# 19-CPLD.net
KiCad netlist of a schematic drawn in Altium Designer
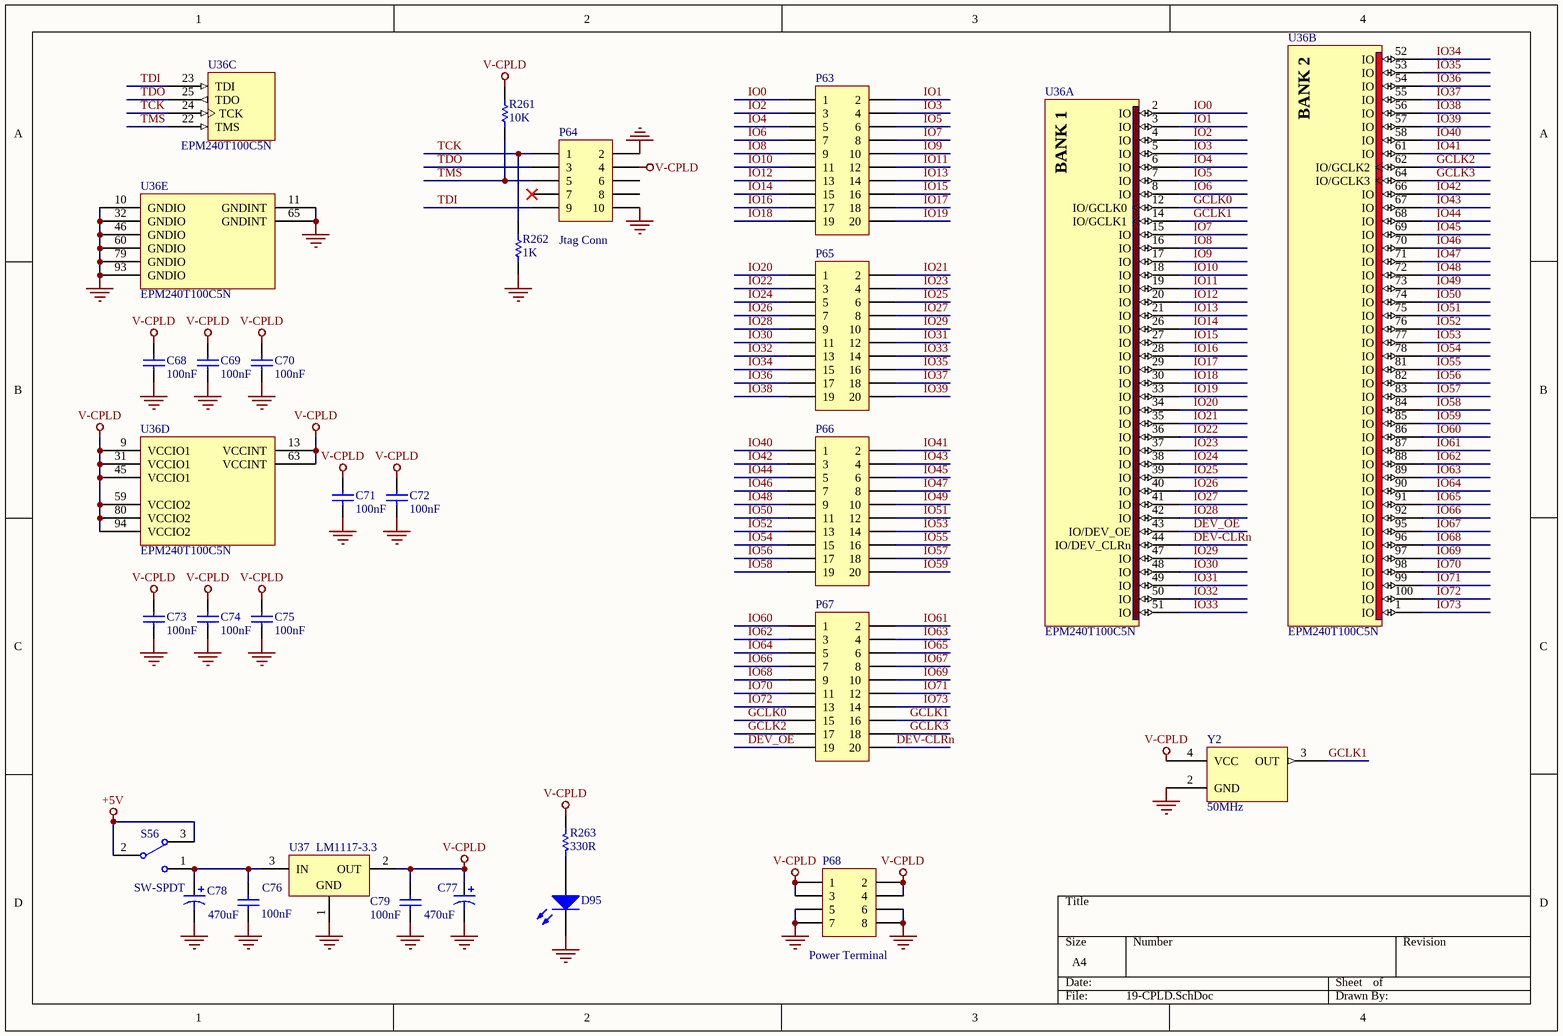
[diagram p0: 19-CPLD.SchDoc]

(export (version "E")
  (design (tool "Eeschema 10.0.6"))
  (components
    (comp (ref "C68")
      (value "100nF")
      (footprint "c-0805")
      (description "Capacitor")
      (fields (field (name "Comment") "104") (field (name "PUBLISHER") "Altium Limited"))
      (libsource (lib "Miscellaneous Devices") (part "Cap"))
    )
    (comp (ref "C69")
      (value "100nF")
      (footprint "c-0805")
      (description "Capacitor")
      (fields (field (name "Comment") "104") (field (name "PUBLISHER") "Altium Limited"))
      (libsource (lib "Miscellaneous Devices") (part "Cap"))
    )
    (comp (ref "C70")
      (value "100nF")
      (footprint "c-0805")
      (description "Capacitor")
      (fields (field (name "Comment") "104") (field (name "PUBLISHER") "Altium Limited"))
      (libsource (lib "Miscellaneous Devices") (part "Cap"))
    )
    (comp (ref "C71")
      (value "100nF")
      (footprint "c-0805")
      (description "Capacitor")
      (fields (field (name "Comment") "104") (field (name "PUBLISHER") "Altium Limited"))
      (libsource (lib "Miscellaneous Devices") (part "Cap"))
    )
    (comp (ref "C72")
      (value "100nF")
      (footprint "c-0805")
      (description "Capacitor")
      (fields (field (name "Comment") "104") (field (name "PUBLISHER") "Altium Limited"))
      (libsource (lib "Miscellaneous Devices") (part "Cap"))
    )
    (comp (ref "C73")
      (value "100nF")
      (footprint "c-0805")
      (description "Capacitor")
      (fields (field (name "Comment") "104") (field (name "PUBLISHER") "Altium Limited"))
      (libsource (lib "Miscellaneous Devices") (part "Cap"))
    )
    (comp (ref "C74")
      (value "100nF")
      (footprint "c-0805")
      (description "Capacitor")
      (fields (field (name "Comment") "104") (field (name "PUBLISHER") "Altium Limited"))
      (libsource (lib "Miscellaneous Devices") (part "Cap"))
    )
    (comp (ref "C75")
      (value "100nF")
      (footprint "c-0805")
      (description "Capacitor")
      (fields (field (name "Comment") "104") (field (name "PUBLISHER") "Altium Limited"))
      (libsource (lib "Miscellaneous Devices") (part "Cap"))
    )
    (comp (ref "C76")
      (value "100nF")
      (footprint "c-0805")
      (description "Capacitor")
      (fields
        (field (name "MANUFACTURER") "Generic Components")
        (field (name "Comment") "104")
        (field (name "PUBLISHER") "Altium Hobart Technology Centre")
      )
      (libsource (lib "Miscellaneous Devices") (part "Cap"))
    )
    (comp (ref "C77")
      (value "470uF")
      (footprint "C-ALU-10x10mm")
      (description "Polarized Capacitor (Radial)")
      (fields (field (name "Comment") "470uF/16V") (field (name "PUBLISHER") "Altium Limited"))
      (libsource (lib "Miscellaneous Devices") (part "Cap Pol1"))
    )
    (comp (ref "C78")
      (value "470uF")
      (footprint "C-ALU-10x10mm")
      (description "Polarized Capacitor (Radial)")
      (fields (field (name "Comment") "470uF/16V") (field (name "PUBLISHER") "Altium Limited"))
      (libsource (lib "Miscellaneous Devices") (part "Cap Pol1"))
    )
    (comp (ref "C79")
      (value "100nF")
      (footprint "c-0805")
      (description "Capacitor")
      (fields
        (field (name "MANUFACTURER") "Generic Components")
        (field (name "Comment") "104")
        (field (name "PUBLISHER") "Altium Hobart Technology Centre")
      )
      (libsource (lib "Miscellaneous Devices") (part "Cap"))
    )
    (comp (ref "D95")
      (value "LED")
      (footprint "LED-3528")
      (description "Typical INFRARED GaAs LED")
      (fields (field (name "PUBLISHER") "Altium Limited"))
      (libsource (lib "Miscellaneous Devices") (part "LED0"))
    )
    (comp (ref "P63")
      (value "H2")
      (footprint "HDR2X10")
      (description "Header, 10-Pin, Dual row")
      (libsource (lib "Miscellaneous Connectors") (part "Header 10X2"))
    )
    (comp (ref "P64")
      (value "Jtag Conn")
      (footprint "HDR2X5")
      (description "Header, 5-Pin, Dual row")
      (fields (field (name "Comment") "IDE5x2"))
      (libsource (lib "Miscellaneous Connectors") (part "Header 5X2"))
    )
    (comp (ref "P65")
      (value "H2")
      (footprint "HDR2X10")
      (description "Header, 10-Pin, Dual row")
      (libsource (lib "Miscellaneous Connectors") (part "Header 10X2"))
    )
    (comp (ref "P66")
      (value "H2")
      (footprint "HDR2X10")
      (description "Header, 10-Pin, Dual row")
      (libsource (lib "Miscellaneous Connectors") (part "Header 10X2"))
    )
    (comp (ref "P67")
      (value "H2")
      (footprint "HDR2X10")
      (description "Header, 10-Pin, Dual row")
      (libsource (lib "Miscellaneous Connectors") (part "Header 10X2"))
    )
    (comp (ref "P68")
      (value "Header 4X2")
      (footprint "HDR2X4")
      (description "Header, 4-Pin, Dual row")
      (fields (field (name "PUBLISHER") "Power Terminal"))
      (libsource (lib "Miscellaneous Connectors") (part "Header 4X2"))
    )
    (comp (ref "R261")
      (value "10K")
      (footprint "r-0805")
      (description "Resistor")
      (fields (field (name "PUBLISHER") "Altium Limited"))
      (libsource (lib "Miscellaneous Devices") (part "Res1"))
    )
    (comp (ref "R262")
      (value "1K")
      (footprint "r-0805")
      (description "Resistor")
      (fields (field (name "PUBLISHER") "Altium Limited"))
      (libsource (lib "Miscellaneous Devices") (part "Res1"))
    )
    (comp (ref "R263")
      (value "330R")
      (footprint "r-0805")
      (description "Resistor")
      (fields (field (name "Comment") "331") (field (name "PUBLISHER") "Altium Limited"))
      (libsource (lib "") (part "Res1_1"))
    )
    (comp (ref "S56")
      (value "SW-SPDT")
      (footprint "SW-DIP1SMD")
      (description "SPDT Subminiature Toggle Switch, Right Angle Mounting, Vertical Actuation")
      (fields (field (name "PUBLISHER") "Altium Limited"))
      (libsource (lib "Miscellaneous Devices") (part "SW-SPDT"))
    )
    (comp (ref "U36")
      (value "EPM240T100C5N")
      (footprint "TQFP100L")
      (fields (field (name "PUBLISHER") "Altium Limited"))
      (libsource (lib "Altera MAX II") (part "EPM240T100C5N"))
    )
    (comp (ref "U37")
      (value "LM1117-3.3")
      (footprint "sot223")
      (description "800mA Low-Dropout Linear Regulator, 3-pin TO-252")
      (fields
        (field (name "PARTNUMBER") "LM1117IDTX-3.3")
        (field (name "MANUFACTURER") "National Semiconductor")
        (field (name "PUBLISHER") "Altium Limited")
      )
      (libsource (lib "NSC LDO") (part "LM1117IDTX-3.3"))
    )
    (comp (ref "Y2")
      (value "50MHz")
      (footprint "xt5032")
      (description "XTAL 50MHz, 4pin")
      (libsource (lib "Dlib") (part "OSC"))
    )
  )
  (nets
    (net (code "1") (name "+5V") (class "Default")
      (node (ref "S56") (pin "2") (pinfunction "2_2") (pintype "passive"))
      (node (ref "S56") (pin "3") (pinfunction "3_3") (pintype "passive"))
    )
    (net (code "2") (name "/DEV-CLRn") (class "Default")
      (node (ref "P67") (pin "20") (pinfunction "20_20") (pintype "passive"))
      (node (ref "U36") (pin "44") (pinfunction "IO/DEV_CLRn_44") (pintype "bidirectional"))
    )
    (net (code "3") (name "/DEV_OE") (class "Default")
      (node (ref "P67") (pin "19") (pinfunction "19_19") (pintype "passive"))
      (node (ref "U36") (pin "43") (pinfunction "IO/DEV_OE_43") (pintype "bidirectional"))
    )
    (net (code "4") (name "/GCLK0") (class "Default")
      (node (ref "P67") (pin "15") (pinfunction "15_15") (pintype "passive"))
      (node (ref "U36") (pin "12") (pinfunction "IO/GCLK0_12") (pintype "bidirectional"))
    )
    (net (code "5") (name "/GCLK1") (class "Default")
      (node (ref "P67") (pin "16") (pinfunction "16_16") (pintype "passive"))
      (node (ref "U36") (pin "14") (pinfunction "IO/GCLK1_14") (pintype "bidirectional"))
      (node (ref "Y2") (pin "3") (pinfunction "OUT_3") (pintype "output"))
    )
    (net (code "6") (name "/GCLK2") (class "Default")
      (node (ref "P67") (pin "17") (pinfunction "17_17") (pintype "passive"))
      (node (ref "U36") (pin "62") (pinfunction "IO/GCLK2_62") (pintype "bidirectional"))
    )
    (net (code "7") (name "/GCLK3") (class "Default")
      (node (ref "P67") (pin "18") (pinfunction "18_18") (pintype "passive"))
      (node (ref "U36") (pin "64") (pinfunction "IO/GCLK3_64") (pintype "bidirectional"))
    )
    (net (code "8") (name "/IO0") (class "Default")
      (node (ref "P63") (pin "1") (pinfunction "1_1") (pintype "passive"))
      (node (ref "U36") (pin "2") (pinfunction "IO_2") (pintype "bidirectional"))
    )
    (net (code "9") (name "/IO1") (class "Default")
      (node (ref "P63") (pin "2") (pinfunction "2_2") (pintype "passive"))
      (node (ref "U36") (pin "3") (pinfunction "IO_3") (pintype "bidirectional"))
    )
    (net (code "10") (name "/IO2") (class "Default")
      (node (ref "P63") (pin "3") (pinfunction "3_3") (pintype "passive"))
      (node (ref "U36") (pin "4") (pinfunction "IO_4") (pintype "bidirectional"))
    )
    (net (code "11") (name "/IO3") (class "Default")
      (node (ref "P63") (pin "4") (pinfunction "4_4") (pintype "passive"))
      (node (ref "U36") (pin "5") (pinfunction "IO_5") (pintype "bidirectional"))
    )
    (net (code "12") (name "/IO4") (class "Default")
      (node (ref "P63") (pin "5") (pinfunction "5_5") (pintype "passive"))
      (node (ref "U36") (pin "6") (pinfunction "IO_6") (pintype "bidirectional"))
    )
    (net (code "13") (name "/IO5") (class "Default")
      (node (ref "P63") (pin "6") (pinfunction "6_6") (pintype "passive"))
      (node (ref "U36") (pin "7") (pinfunction "IO_7") (pintype "bidirectional"))
    )
    (net (code "14") (name "/IO6") (class "Default")
      (node (ref "P63") (pin "7") (pinfunction "7_7") (pintype "passive"))
      (node (ref "U36") (pin "8") (pinfunction "IO_8") (pintype "bidirectional"))
    )
    (net (code "15") (name "/IO7") (class "Default")
      (node (ref "P63") (pin "8") (pinfunction "8_8") (pintype "passive"))
      (node (ref "U36") (pin "15") (pinfunction "IO_15") (pintype "bidirectional"))
    )
    (net (code "16") (name "/IO8") (class "Default")
      (node (ref "P63") (pin "9") (pinfunction "9_9") (pintype "passive"))
      (node (ref "U36") (pin "16") (pinfunction "IO_16") (pintype "bidirectional"))
    )
    (net (code "17") (name "/IO9") (class "Default")
      (node (ref "P63") (pin "10") (pinfunction "10_10") (pintype "passive"))
      (node (ref "U36") (pin "17") (pinfunction "IO_17") (pintype "bidirectional"))
    )
    (net (code "18") (name "/IO10") (class "Default")
      (node (ref "P63") (pin "11") (pinfunction "11_11") (pintype "passive"))
      (node (ref "U36") (pin "18") (pinfunction "IO_18") (pintype "bidirectional"))
    )
    (net (code "19") (name "/IO11") (class "Default")
      (node (ref "P63") (pin "12") (pinfunction "12_12") (pintype "passive"))
      (node (ref "U36") (pin "19") (pinfunction "IO_19") (pintype "bidirectional"))
    )
    (net (code "20") (name "/IO12") (class "Default")
      (node (ref "P63") (pin "13") (pinfunction "13_13") (pintype "passive"))
      (node (ref "U36") (pin "20") (pinfunction "IO_20") (pintype "bidirectional"))
    )
    (net (code "21") (name "/IO13") (class "Default")
      (node (ref "P63") (pin "14") (pinfunction "14_14") (pintype "passive"))
      (node (ref "U36") (pin "21") (pinfunction "IO_21") (pintype "bidirectional"))
    )
    (net (code "22") (name "/IO14") (class "Default")
      (node (ref "P63") (pin "15") (pinfunction "15_15") (pintype "passive"))
      (node (ref "U36") (pin "26") (pinfunction "IO_26") (pintype "bidirectional"))
    )
    (net (code "23") (name "/IO15") (class "Default")
      (node (ref "P63") (pin "16") (pinfunction "16_16") (pintype "passive"))
      (node (ref "U36") (pin "27") (pinfunction "IO_27") (pintype "bidirectional"))
    )
    (net (code "24") (name "/IO16") (class "Default")
      (node (ref "P63") (pin "17") (pinfunction "17_17") (pintype "passive"))
      (node (ref "U36") (pin "28") (pinfunction "IO_28") (pintype "bidirectional"))
    )
    (net (code "25") (name "/IO17") (class "Default")
      (node (ref "P63") (pin "18") (pinfunction "18_18") (pintype "passive"))
      (node (ref "U36") (pin "29") (pinfunction "IO_29") (pintype "bidirectional"))
    )
    (net (code "26") (name "/IO18") (class "Default")
      (node (ref "P63") (pin "19") (pinfunction "19_19") (pintype "passive"))
      (node (ref "U36") (pin "30") (pinfunction "IO_30") (pintype "bidirectional"))
    )
    (net (code "27") (name "/IO19") (class "Default")
      (node (ref "P63") (pin "20") (pinfunction "20_20") (pintype "passive"))
      (node (ref "U36") (pin "33") (pinfunction "IO_33") (pintype "bidirectional"))
    )
    (net (code "28") (name "/IO20") (class "Default")
      (node (ref "P65") (pin "1") (pinfunction "1_1") (pintype "passive"))
      (node (ref "U36") (pin "34") (pinfunction "IO_34") (pintype "bidirectional"))
    )
    (net (code "29") (name "/IO21") (class "Default")
      (node (ref "P65") (pin "2") (pinfunction "2_2") (pintype "passive"))
      (node (ref "U36") (pin "35") (pinfunction "IO_35") (pintype "bidirectional"))
    )
    (net (code "30") (name "/IO22") (class "Default")
      (node (ref "P65") (pin "3") (pinfunction "3_3") (pintype "passive"))
      (node (ref "U36") (pin "36") (pinfunction "IO_36") (pintype "bidirectional"))
    )
    (net (code "31") (name "/IO23") (class "Default")
      (node (ref "P65") (pin "4") (pinfunction "4_4") (pintype "passive"))
      (node (ref "U36") (pin "37") (pinfunction "IO_37") (pintype "bidirectional"))
    )
    (net (code "32") (name "/IO24") (class "Default")
      (node (ref "P65") (pin "5") (pinfunction "5_5") (pintype "passive"))
      (node (ref "U36") (pin "38") (pinfunction "IO_38") (pintype "bidirectional"))
    )
    (net (code "33") (name "/IO25") (class "Default")
      (node (ref "P65") (pin "6") (pinfunction "6_6") (pintype "passive"))
      (node (ref "U36") (pin "39") (pinfunction "IO_39") (pintype "bidirectional"))
    )
    (net (code "34") (name "/IO26") (class "Default")
      (node (ref "P65") (pin "7") (pinfunction "7_7") (pintype "passive"))
      (node (ref "U36") (pin "40") (pinfunction "IO_40") (pintype "bidirectional"))
    )
    (net (code "35") (name "/IO27") (class "Default")
      (node (ref "P65") (pin "8") (pinfunction "8_8") (pintype "passive"))
      (node (ref "U36") (pin "41") (pinfunction "IO_41") (pintype "bidirectional"))
    )
    (net (code "36") (name "/IO28") (class "Default")
      (node (ref "P65") (pin "9") (pinfunction "9_9") (pintype "passive"))
      (node (ref "U36") (pin "42") (pinfunction "IO_42") (pintype "bidirectional"))
    )
    (net (code "37") (name "/IO29") (class "Default")
      (node (ref "P65") (pin "10") (pinfunction "10_10") (pintype "passive"))
      (node (ref "U36") (pin "47") (pinfunction "IO_47") (pintype "bidirectional"))
    )
    (net (code "38") (name "/IO30") (class "Default")
      (node (ref "P65") (pin "11") (pinfunction "11_11") (pintype "passive"))
      (node (ref "U36") (pin "48") (pinfunction "IO_48") (pintype "bidirectional"))
    )
    (net (code "39") (name "/IO31") (class "Default")
      (node (ref "P65") (pin "12") (pinfunction "12_12") (pintype "passive"))
      (node (ref "U36") (pin "49") (pinfunction "IO_49") (pintype "bidirectional"))
    )
    (net (code "40") (name "/IO32") (class "Default")
      (node (ref "P65") (pin "13") (pinfunction "13_13") (pintype "passive"))
      (node (ref "U36") (pin "50") (pinfunction "IO_50") (pintype "bidirectional"))
    )
    (net (code "41") (name "/IO33") (class "Default")
      (node (ref "P65") (pin "14") (pinfunction "14_14") (pintype "passive"))
      (node (ref "U36") (pin "51") (pinfunction "IO_51") (pintype "bidirectional"))
    )
    (net (code "42") (name "/IO34") (class "Default")
      (node (ref "P65") (pin "15") (pinfunction "15_15") (pintype "passive"))
      (node (ref "U36") (pin "52") (pinfunction "IO_52") (pintype "bidirectional"))
    )
    (net (code "43") (name "/IO35") (class "Default")
      (node (ref "P65") (pin "16") (pinfunction "16_16") (pintype "passive"))
      (node (ref "U36") (pin "53") (pinfunction "IO_53") (pintype "bidirectional"))
    )
    (net (code "44") (name "/IO36") (class "Default")
      (node (ref "P65") (pin "17") (pinfunction "17_17") (pintype "passive"))
      (node (ref "U36") (pin "54") (pinfunction "IO_54") (pintype "bidirectional"))
    )
    (net (code "45") (name "/IO37") (class "Default")
      (node (ref "P65") (pin "18") (pinfunction "18_18") (pintype "passive"))
      (node (ref "U36") (pin "55") (pinfunction "IO_55") (pintype "bidirectional"))
    )
    (net (code "46") (name "/IO38") (class "Default")
      (node (ref "P65") (pin "19") (pinfunction "19_19") (pintype "passive"))
      (node (ref "U36") (pin "56") (pinfunction "IO_56") (pintype "bidirectional"))
    )
    (net (code "47") (name "/IO39") (class "Default")
      (node (ref "P65") (pin "20") (pinfunction "20_20") (pintype "passive"))
      (node (ref "U36") (pin "57") (pinfunction "IO_57") (pintype "bidirectional"))
    )
    (net (code "48") (name "/IO40") (class "Default")
      (node (ref "P66") (pin "1") (pinfunction "1_1") (pintype "passive"))
      (node (ref "U36") (pin "58") (pinfunction "IO_58") (pintype "bidirectional"))
    )
    (net (code "49") (name "/IO41") (class "Default")
      (node (ref "P66") (pin "2") (pinfunction "2_2") (pintype "passive"))
      (node (ref "U36") (pin "61") (pinfunction "IO_61") (pintype "bidirectional"))
    )
    (net (code "50") (name "/IO42") (class "Default")
      (node (ref "P66") (pin "3") (pinfunction "3_3") (pintype "passive"))
      (node (ref "U36") (pin "66") (pinfunction "IO_66") (pintype "bidirectional"))
    )
    (net (code "51") (name "/IO43") (class "Default")
      (node (ref "P66") (pin "4") (pinfunction "4_4") (pintype "passive"))
      (node (ref "U36") (pin "67") (pinfunction "IO_67") (pintype "bidirectional"))
    )
    (net (code "52") (name "/IO44") (class "Default")
      (node (ref "P66") (pin "5") (pinfunction "5_5") (pintype "passive"))
      (node (ref "U36") (pin "68") (pinfunction "IO_68") (pintype "bidirectional"))
    )
    (net (code "53") (name "/IO45") (class "Default")
      (node (ref "P66") (pin "6") (pinfunction "6_6") (pintype "passive"))
      (node (ref "U36") (pin "69") (pinfunction "IO_69") (pintype "bidirectional"))
    )
    (net (code "54") (name "/IO46") (class "Default")
      (node (ref "P66") (pin "7") (pinfunction "7_7") (pintype "passive"))
      (node (ref "U36") (pin "70") (pinfunction "IO_70") (pintype "bidirectional"))
    )
    (net (code "55") (name "/IO47") (class "Default")
      (node (ref "P66") (pin "8") (pinfunction "8_8") (pintype "passive"))
      (node (ref "U36") (pin "71") (pinfunction "IO_71") (pintype "bidirectional"))
    )
    (net (code "56") (name "/IO48") (class "Default")
      (node (ref "P66") (pin "9") (pinfunction "9_9") (pintype "passive"))
      (node (ref "U36") (pin "72") (pinfunction "IO_72") (pintype "bidirectional"))
    )
    (net (code "57") (name "/IO49") (class "Default")
      (node (ref "P66") (pin "10") (pinfunction "10_10") (pintype "passive"))
      (node (ref "U36") (pin "73") (pinfunction "IO_73") (pintype "bidirectional"))
    )
    (net (code "58") (name "/IO50") (class "Default")
      (node (ref "P66") (pin "11") (pinfunction "11_11") (pintype "passive"))
      (node (ref "U36") (pin "74") (pinfunction "IO_74") (pintype "bidirectional"))
    )
    (net (code "59") (name "/IO51") (class "Default")
      (node (ref "P66") (pin "12") (pinfunction "12_12") (pintype "passive"))
      (node (ref "U36") (pin "75") (pinfunction "IO_75") (pintype "bidirectional"))
    )
    (net (code "60") (name "/IO52") (class "Default")
      (node (ref "P66") (pin "13") (pinfunction "13_13") (pintype "passive"))
      (node (ref "U36") (pin "76") (pinfunction "IO_76") (pintype "bidirectional"))
    )
    (net (code "61") (name "/IO53") (class "Default")
      (node (ref "P66") (pin "14") (pinfunction "14_14") (pintype "passive"))
      (node (ref "U36") (pin "77") (pinfunction "IO_77") (pintype "bidirectional"))
    )
    (net (code "62") (name "/IO54") (class "Default")
      (node (ref "P66") (pin "15") (pinfunction "15_15") (pintype "passive"))
      (node (ref "U36") (pin "78") (pinfunction "IO_78") (pintype "bidirectional"))
    )
    (net (code "63") (name "/IO55") (class "Default")
      (node (ref "P66") (pin "16") (pinfunction "16_16") (pintype "passive"))
      (node (ref "U36") (pin "81") (pinfunction "IO_81") (pintype "bidirectional"))
    )
    (net (code "64") (name "/IO56") (class "Default")
      (node (ref "P66") (pin "17") (pinfunction "17_17") (pintype "passive"))
      (node (ref "U36") (pin "82") (pinfunction "IO_82") (pintype "bidirectional"))
    )
    (net (code "65") (name "/IO57") (class "Default")
      (node (ref "P66") (pin "18") (pinfunction "18_18") (pintype "passive"))
      (node (ref "U36") (pin "83") (pinfunction "IO_83") (pintype "bidirectional"))
    )
    (net (code "66") (name "/IO58") (class "Default")
      (node (ref "P66") (pin "19") (pinfunction "19_19") (pintype "passive"))
      (node (ref "U36") (pin "84") (pinfunction "IO_84") (pintype "bidirectional"))
    )
    (net (code "67") (name "/IO59") (class "Default")
      (node (ref "P66") (pin "20") (pinfunction "20_20") (pintype "passive"))
      (node (ref "U36") (pin "85") (pinfunction "IO_85") (pintype "bidirectional"))
    )
    (net (code "68") (name "/IO60") (class "Default")
      (node (ref "P67") (pin "1") (pinfunction "1_1") (pintype "passive"))
      (node (ref "U36") (pin "86") (pinfunction "IO_86") (pintype "bidirectional"))
    )
    (net (code "69") (name "/IO61") (class "Default")
      (node (ref "P67") (pin "2") (pinfunction "2_2") (pintype "passive"))
      (node (ref "U36") (pin "87") (pinfunction "IO_87") (pintype "bidirectional"))
    )
    (net (code "70") (name "/IO62") (class "Default")
      (node (ref "P67") (pin "3") (pinfunction "3_3") (pintype "passive"))
      (node (ref "U36") (pin "88") (pinfunction "IO_88") (pintype "bidirectional"))
    )
    (net (code "71") (name "/IO63") (class "Default")
      (node (ref "P67") (pin "4") (pinfunction "4_4") (pintype "passive"))
      (node (ref "U36") (pin "89") (pinfunction "IO_89") (pintype "bidirectional"))
    )
    (net (code "72") (name "/IO64") (class "Default")
      (node (ref "P67") (pin "5") (pinfunction "5_5") (pintype "passive"))
      (node (ref "U36") (pin "90") (pinfunction "IO_90") (pintype "bidirectional"))
    )
    (net (code "73") (name "/IO65") (class "Default")
      (node (ref "P67") (pin "6") (pinfunction "6_6") (pintype "passive"))
      (node (ref "U36") (pin "91") (pinfunction "IO_91") (pintype "bidirectional"))
    )
    (net (code "74") (name "/IO66") (class "Default")
      (node (ref "P67") (pin "7") (pinfunction "7_7") (pintype "passive"))
      (node (ref "U36") (pin "92") (pinfunction "IO_92") (pintype "bidirectional"))
    )
    (net (code "75") (name "/IO67") (class "Default")
      (node (ref "P67") (pin "8") (pinfunction "8_8") (pintype "passive"))
      (node (ref "U36") (pin "95") (pinfunction "IO_95") (pintype "bidirectional"))
    )
    (net (code "76") (name "/IO68") (class "Default")
      (node (ref "P67") (pin "9") (pinfunction "9_9") (pintype "passive"))
      (node (ref "U36") (pin "96") (pinfunction "IO_96") (pintype "bidirectional"))
    )
    (net (code "77") (name "/IO69") (class "Default")
      (node (ref "P67") (pin "10") (pinfunction "10_10") (pintype "passive"))
      (node (ref "U36") (pin "97") (pinfunction "IO_97") (pintype "bidirectional"))
    )
    (net (code "78") (name "/IO70") (class "Default")
      (node (ref "P67") (pin "11") (pinfunction "11_11") (pintype "passive"))
      (node (ref "U36") (pin "98") (pinfunction "IO_98") (pintype "bidirectional"))
    )
    (net (code "79") (name "/IO71") (class "Default")
      (node (ref "P67") (pin "12") (pinfunction "12_12") (pintype "passive"))
      (node (ref "U36") (pin "99") (pinfunction "IO_99") (pintype "bidirectional"))
    )
    (net (code "80") (name "/IO72") (class "Default")
      (node (ref "P67") (pin "13") (pinfunction "13_13") (pintype "passive"))
      (node (ref "U36") (pin "100") (pinfunction "IO_100") (pintype "bidirectional"))
    )
    (net (code "81") (name "/IO73") (class "Default")
      (node (ref "P67") (pin "14") (pinfunction "14_14") (pintype "passive"))
      (node (ref "U36") (pin "1") (pinfunction "IO_1") (pintype "bidirectional"))
    )
    (net (code "82") (name "/TCK") (class "Default")
      (node (ref "P64") (pin "1") (pinfunction "1_1") (pintype "passive"))
      (node (ref "R262") (pin "1") (pinfunction "1_1") (pintype "passive"))
      (node (ref "U36") (pin "24") (pinfunction "TCK_24") (pintype "input"))
    )
    (net (code "83") (name "/TDI") (class "Default")
      (node (ref "P64") (pin "9") (pinfunction "9_9") (pintype "passive"))
      (node (ref "U36") (pin "23") (pinfunction "TDI_23") (pintype "input"))
    )
    (net (code "84") (name "/TDO") (class "Default")
      (node (ref "P64") (pin "3") (pinfunction "3_3") (pintype "passive"))
      (node (ref "U36") (pin "25") (pinfunction "TDO_25") (pintype "output"))
    )
    (net (code "85") (name "/TMS") (class "Default")
      (node (ref "P64") (pin "5") (pinfunction "5_5") (pintype "passive"))
      (node (ref "R261") (pin "2") (pinfunction "2_2") (pintype "passive"))
      (node (ref "U36") (pin "22") (pinfunction "TMS_22") (pintype "input"))
    )
    (net (code "86") (name "GND") (class "Default")
      (node (ref "C68") (pin "2") (pinfunction "2_2") (pintype "passive"))
      (node (ref "C69") (pin "2") (pinfunction "2_2") (pintype "passive"))
      (node (ref "C70") (pin "2") (pinfunction "2_2") (pintype "passive"))
      (node (ref "C71") (pin "2") (pinfunction "2_2") (pintype "passive"))
      (node (ref "C72") (pin "2") (pinfunction "2_2") (pintype "passive"))
      (node (ref "C73") (pin "2") (pinfunction "2_2") (pintype "passive"))
      (node (ref "C74") (pin "2") (pinfunction "2_2") (pintype "passive"))
      (node (ref "C75") (pin "2") (pinfunction "2_2") (pintype "passive"))
      (node (ref "C76") (pin "1") (pinfunction "1_1") (pintype "passive"))
      (node (ref "C77") (pin "2") (pinfunction "2_2") (pintype "passive"))
      (node (ref "C78") (pin "2") (pinfunction "2_2") (pintype "passive"))
      (node (ref "C79") (pin "1") (pinfunction "1_1") (pintype "passive"))
      (node (ref "D95") (pin "2") (pinfunction "K_2") (pintype "passive"))
      (node (ref "P64") (pin "10") (pinfunction "10_10") (pintype "passive"))
      (node (ref "P64") (pin "2") (pinfunction "2_2") (pintype "passive"))
      (node (ref "P68") (pin "5") (pinfunction "5_5") (pintype "passive"))
      (node (ref "P68") (pin "6") (pinfunction "6_6") (pintype "passive"))
      (node (ref "P68") (pin "7") (pinfunction "7_7") (pintype "passive"))
      (node (ref "P68") (pin "8") (pinfunction "8_8") (pintype "passive"))
      (node (ref "R262") (pin "2") (pinfunction "2_2") (pintype "passive"))
      (node (ref "U36") (pin "10") (pinfunction "GNDIO_10") (pintype "power_in"))
      (node (ref "U36") (pin "11") (pinfunction "GNDINT_11") (pintype "power_in"))
      (node (ref "U36") (pin "32") (pinfunction "GNDIO_32") (pintype "power_in"))
      (node (ref "U36") (pin "46") (pinfunction "GNDIO_46") (pintype "power_in"))
      (node (ref "U36") (pin "60") (pinfunction "GNDIO_60") (pintype "power_in"))
      (node (ref "U36") (pin "65") (pinfunction "GNDINT_65") (pintype "power_in"))
      (node (ref "U36") (pin "79") (pinfunction "GNDIO_79") (pintype "power_in"))
      (node (ref "U36") (pin "93") (pinfunction "GNDIO_93") (pintype "power_in"))
      (node (ref "U37") (pin "1") (pinfunction "GND_1") (pintype "power_in"))
      (node (ref "Y2") (pin "2") (pinfunction "GND_2") (pintype "power_in"))
    )
    (net (code "87") (name "Net-(D95-A)") (class "Default")
      (node (ref "D95") (pin "1") (pinfunction "A_1") (pintype "passive"))
      (node (ref "R263") (pin "2") (pinfunction "2_2") (pintype "passive"))
    )
    (net (code "88") (name "Net-(U37-IN)") (class "Default")
      (node (ref "C76") (pin "2") (pinfunction "2_2") (pintype "passive"))
      (node (ref "C78") (pin "1") (pinfunction "1_1") (pintype "passive"))
      (node (ref "S56") (pin "1") (pinfunction "1_1") (pintype "passive"))
      (node (ref "U37") (pin "3") (pinfunction "IN_3") (pintype "power_in"))
    )
    (net (code "89") (name "V-CPLD") (class "Default")
      (node (ref "C68") (pin "1") (pinfunction "1_1") (pintype "passive"))
      (node (ref "C69") (pin "1") (pinfunction "1_1") (pintype "passive"))
      (node (ref "C70") (pin "1") (pinfunction "1_1") (pintype "passive"))
      (node (ref "C71") (pin "1") (pinfunction "1_1") (pintype "passive"))
      (node (ref "C72") (pin "1") (pinfunction "1_1") (pintype "passive"))
      (node (ref "C73") (pin "1") (pinfunction "1_1") (pintype "passive"))
      (node (ref "C74") (pin "1") (pinfunction "1_1") (pintype "passive"))
      (node (ref "C75") (pin "1") (pinfunction "1_1") (pintype "passive"))
      (node (ref "C77") (pin "1") (pinfunction "1_1") (pintype "passive"))
      (node (ref "C79") (pin "2") (pinfunction "2_2") (pintype "passive"))
      (node (ref "P64") (pin "4") (pinfunction "4_4") (pintype "passive"))
      (node (ref "P68") (pin "1") (pinfunction "1_1") (pintype "passive"))
      (node (ref "P68") (pin "2") (pinfunction "2_2") (pintype "passive"))
      (node (ref "P68") (pin "3") (pinfunction "3_3") (pintype "passive"))
      (node (ref "P68") (pin "4") (pinfunction "4_4") (pintype "passive"))
      (node (ref "R261") (pin "1") (pinfunction "1_1") (pintype "passive"))
      (node (ref "R263") (pin "1") (pinfunction "1_1") (pintype "passive"))
      (node (ref "U36") (pin "13") (pinfunction "VCCINT_13") (pintype "power_in"))
      (node (ref "U36") (pin "31") (pinfunction "VCCIO1_31") (pintype "power_in"))
      (node (ref "U36") (pin "45") (pinfunction "VCCIO1_45") (pintype "power_in"))
      (node (ref "U36") (pin "59") (pinfunction "VCCIO2_59") (pintype "power_in"))
      (node (ref "U36") (pin "63") (pinfunction "VCCINT_63") (pintype "power_in"))
      (node (ref "U36") (pin "80") (pinfunction "VCCIO2_80") (pintype "power_in"))
      (node (ref "U36") (pin "9") (pinfunction "VCCIO1_9") (pintype "power_in"))
      (node (ref "U36") (pin "94") (pinfunction "VCCIO2_94") (pintype "power_in"))
      (node (ref "U37") (pin "2") (pinfunction "OUT_2") (pintype "power_in"))
      (node (ref "Y2") (pin "4") (pinfunction "VCC_4") (pintype "power_in"))
    )
    (net (code "90") (name "unconnected-(P64-Pad6)") (class "Default")
      (node (ref "P64") (pin "6") (pinfunction "6_6") (pintype "passive"))
    )
    (net (code "91") (name "unconnected-(P64-Pad7)") (class "Default")
      (node (ref "P64") (pin "7") (pinfunction "7_7") (pintype "passive+no_connect"))
    )
    (net (code "92") (name "unconnected-(P64-Pad8)") (class "Default")
      (node (ref "P64") (pin "8") (pinfunction "8_8") (pintype "passive"))
    )
    (net (code "93") (name "unconnected-(Y2-NC-Pad1)") (class "Default")
      (node (ref "Y2") (pin "1") (pinfunction "NC_1") (pintype "passive"))
    )
  )
)
